# Sheet_brainstorm1.net
KiCad netlist of a schematic drawn in Altium Designer
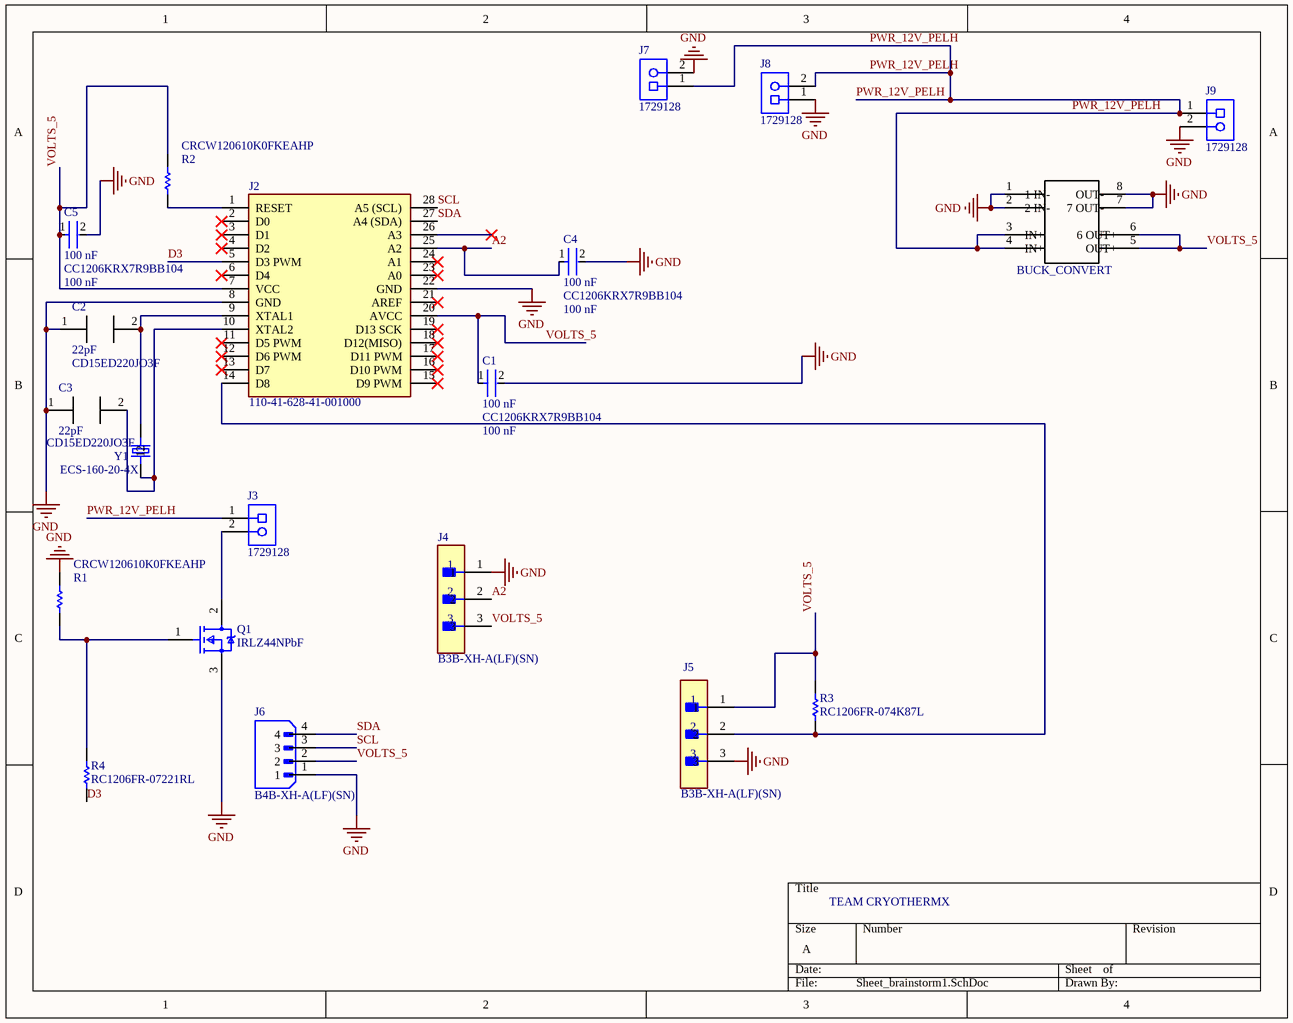
[diagram p0: Sheet_brainstorm1.SchDoc]

(export (version "E")
  (design (tool "Eeschema 10.0.6"))
  (components
    (comp (ref "BUCK_CONVERT")
      (value "buck convertter")
      (footprint "BUCK_CONVERTER")
      (libsource (lib "Integrated_Library_brainstorm1") (part "buck convertter"))
    )
    (comp (ref "C1")
      (value "100 nF")
      (footprint "FP-CC1206-1_25-MFG")
      (description "CAP CER 0.1UF 50V X7R 1206")
      (fields
        (field (name "OCTOPART") "https://octopart.com/cc1206krx7r9bb104-yageo-39467816")
        (field (name "ALTIUM_VALUE") "100 nF")
        (field (name "TOLERANCE") "0.1")
        (field (name "MANUFACTURER PART NUMBER") "CC1206KRX7R9BB104")
      )
      (libsource (lib "Altium Content Vault") (part "11868f565c42a9108669ba33697ecf6"))
    )
    (comp (ref "C2")
      (value "22pF")
      (footprint "PCBComponent_1")
      (description "Mica Capacitor, Mica, 500V, 5% +Tol, 5% -Tol, -20/+100ppm/Cel TC, 0.000022uF, Through Hole Mount")
      (fields
        (field (name "MANUFACTURER") "Cornell Dubilier")
        (field (name "MANUFACTURER PART NUMBER") "CD15ED220JO3F")
      )
      (libsource (lib "Integrated_Library_brainstorm1") (part "CD15ED220JO3F"))
    )
    (comp (ref "C3")
      (value "22pF")
      (footprint "PCBComponent_1")
      (description "Mica Capacitor, Mica, 500V, 5% +Tol, 5% -Tol, -20/+100ppm/Cel TC, 0.000022uF, Through Hole Mount")
      (fields
        (field (name "MANUFACTURER") "Cornell Dubilier")
        (field (name "MANUFACTURER PART NUMBER") "CD15ED220JO3F")
      )
      (libsource (lib "Integrated_Library_brainstorm1") (part "CD15ED220JO3F"))
    )
    (comp (ref "C4")
      (value "100 nF")
      (footprint "FP-CC1206-1_25-MFG")
      (description "CAP CER 0.1UF 50V X7R 1206")
      (fields
        (field (name "OCTOPART") "https://octopart.com/cc1206krx7r9bb104-yageo-39467816")
        (field (name "ALTIUM_VALUE") "100 nF")
        (field (name "TOLERANCE") "0.1")
        (field (name "MANUFACTURER PART NUMBER") "CC1206KRX7R9BB104")
      )
      (libsource (lib "Altium Content Vault") (part "11868f565c42a9108669ba33697ecf6"))
    )
    (comp (ref "C5")
      (value "100 nF")
      (footprint "FP-CC1206-1_25-MFG")
      (description "CAP CER 0.1UF 50V X7R 1206")
      (fields
        (field (name "OCTOPART") "https://octopart.com/cc1206krx7r9bb104-yageo-39467816")
        (field (name "ALTIUM_VALUE") "100 nF")
        (field (name "TOLERANCE") "0.1")
        (field (name "MANUFACTURER PART NUMBER") "CC1206KRX7R9BB104")
      )
      (libsource (lib "Altium Content Vault") (part "11868f565c42a9108669ba33697ecf6"))
    )
    (comp (ref "J2")
      (value "110-41-628-41-001000")
      (footprint "DIPS1524W50P254L3556H419Q28")
      (description "28 (2 x 14) Pos DIP, 0.6 (15.24mm) Row Spacing Socket Gold Through Hole")
      (fields (field (name "MF") "Mill-Max"))
      (libsource (lib "110-41-628-41-001000") (part "110-41-628-41-001000"))
    )
    (comp (ref "J3")
      (value "1729128")
      (footprint "PHOE-1729128-2_V")
      (description "PCB Terminal Block, 13.5 A, 400 V, 2-Pin THD, RoHS, Bulk")
      (fields (field (name "MANUFACTURER") "Phoenix Contact"))
      (libsource (lib "Altium Content Vault") (part "CN-2P-F-R2"))
    )
    (comp (ref "J4")
      (value "B3B-XH-A(LF)(SN)")
      (footprint "FP-B3B-XH-A_LF_SN-MFG")
      (description "CONN HEADER VERT 3POS 2.5MM")
      (libsource (lib "Altium Content Vault") (part "0d3f023dd272f625e17a2be33dea85f"))
    )
    (comp (ref "J5")
      (value "B3B-XH-A(LF)(SN)")
      (footprint "FP-B3B-XH-A_LF_SN-MFG")
      (description "CONN HEADER VERT 3POS 2.5MM")
      (libsource (lib "Altium Content Vault") (part "0d3f023dd272f625e17a2be33dea85f"))
    )
    (comp (ref "J6")
      (value "B4B-XH-A(LF)(SN)")
      (footprint "JST_B4B-XH-A(LF)(SN)")
      (description "Connector Header Through Hole 4 position 0.098 (2.50mm)")
      (fields (field (name "MF") "JST Sales"))
      (libsource (lib "B4B-XH-A_LF__SN_") (part "B4B-XH-A(LF)(SN)"))
    )
    (comp (ref "J7")
      (value "1729128")
      (footprint "PHOE-1729128-2_V")
      (description "PCB Terminal Block, 13.5 A, 400 V, 2-Pin THD, RoHS, Bulk")
      (fields (field (name "MANUFACTURER") "Phoenix Contact"))
      (libsource (lib "") (part "CN-2P-F-R2_1"))
    )
    (comp (ref "J8")
      (value "1729128")
      (footprint "PHOE-1729128-2_V")
      (description "PCB Terminal Block, 13.5 A, 400 V, 2-Pin THD, RoHS, Bulk")
      (fields (field (name "MANUFACTURER") "Phoenix Contact"))
      (libsource (lib "") (part "CN-2P-F-R2_1"))
    )
    (comp (ref "J9")
      (value "1729128")
      (footprint "PHOE-1729128-2_V")
      (description "PCB Terminal Block, 13.5 A, 400 V, 2-Pin THD, RoHS, Bulk")
      (fields (field (name "MANUFACTURER") "Phoenix Contact"))
      (libsource (lib "Altium Content Vault") (part "CN-2P-F-R2"))
    )
    (comp (ref "Q1")
      (value "IRLZ44NPbF")
      (footprint "FP-PG-TO220-3-MFG")
      (description "MOSFET N-CH 55V 47A TO220AB")
      (libsource (lib "Altium Content Vault") (part "b09f7f152735e370c1ea22a33fa83d6"))
    )
    (comp (ref "R1")
      (value "CRCW120610K0FKEAHP")
      (footprint "RESC3116X65X50NL20T20")
      (description "10KOhm R -CRCW120610K0FKEAHP")
      (fields (field (name "MANUFACTURER") "Vishay Dale"))
      (libsource (lib "Altium Content Vault") (part "RES"))
    )
    (comp (ref "R2")
      (value "CRCW120610K0FKEAHP")
      (footprint "RESC3116X65X50NL20T20")
      (description "10KOhm R -CRCW120610K0FKEAHP")
      (fields (field (name "MANUFACTURER") "Vishay Dale"))
      (libsource (lib "Altium Content Vault") (part "RES"))
    )
    (comp (ref "R3")
      (value "RC1206FR-074K87L")
      (footprint "RESC3116X65X40ML10T20")
      (fields (field (name "MANUFACTURER") "Yageo"))
      (libsource (lib "Altium Content Vault") (part "RES"))
    )
    (comp (ref "R4")
      (value "RC1206FR-07221RL")
      (footprint "RESC3116X65X40LL10T20")
      (fields (field (name "MANUFACTURER") "Yageo"))
      (libsource (lib "Altium Content Vault") (part "RES"))
    )
    (comp (ref "Y1")
      (value "ECS-160-20-4X")
      (footprint "XTAL_ECS-160-20-4X")
      (description "16 MHz Â±30ppm Crystal 20pF 40 Ohms HC-49/US")
      (fields (field (name "MF") "ECS Inc."))
      (libsource (lib "ECS-160-20-4X") (part "ECS-160-20-4X"))
    )
  )
  (nets
    (net (code "2") (name "/A2") (class "Default")
      (node (ref "C4") (pin "1") (pinfunction "1_1") (pintype "passive"))
      (node (ref "J2") (pin "25") (pinfunction "A2_25") (pintype "passive"))
      (node (ref "J4") (pin "2") (pinfunction "2_2") (pintype "passive"))
    )
    (net (code "3") (name "/D3") (class "Default")
      (node (ref "J2") (pin "5") (pinfunction "D3_PWM_5") (pintype "passive"))
      (node (ref "R4") (pin "1") (pinfunction "1_1") (pintype "passive"))
    )
    (net (code "4") (name "/PWR_12V_PELH") (class "Default")
      (node (ref "BUCK_CONVERT") (pin "3") (pinfunction "IN+_3") (pintype "passive"))
      (node (ref "BUCK_CONVERT") (pin "4") (pinfunction "IN+_4") (pintype "passive"))
      (node (ref "J3") (pin "1") (pinfunction "1_1") (pintype "passive"))
      (node (ref "J7") (pin "1") (pinfunction "1_1") (pintype "passive"))
      (node (ref "J8") (pin "2") (pinfunction "2_2") (pintype "passive"))
      (node (ref "J9") (pin "1") (pinfunction "1_1") (pintype "passive"))
    )
    (net (code "5") (name "/SCL") (class "Default")
      (node (ref "J2") (pin "28") (pinfunction "A5_(SCL)_28") (pintype "passive"))
      (node (ref "J6") (pin "3") (pinfunction "3_3") (pintype "passive"))
    )
    (net (code "6") (name "/SDA") (class "Default")
      (node (ref "J2") (pin "27") (pinfunction "A4_(SDA)_27") (pintype "passive"))
      (node (ref "J6") (pin "4") (pinfunction "4_4") (pintype "passive"))
    )
    (net (code "7") (name "/VOLTS_5") (class "Default")
      (node (ref "BUCK_CONVERT") (pin "5") (pinfunction "OUT+_5") (pintype "passive"))
      (node (ref "BUCK_CONVERT") (pin "6") (pinfunction "6_OUT+_6") (pintype "passive"))
      (node (ref "C1") (pin "1") (pinfunction "1_1") (pintype "passive"))
      (node (ref "C5") (pin "1") (pinfunction "1_1") (pintype "passive"))
      (node (ref "J2") (pin "20") (pinfunction "AVCC_20") (pintype "passive"))
      (node (ref "J2") (pin "7") (pinfunction "VCC_7") (pintype "passive"))
      (node (ref "J4") (pin "3") (pinfunction "3_3") (pintype "passive"))
      (node (ref "J5") (pin "1") (pinfunction "1_1") (pintype "passive"))
      (node (ref "J6") (pin "2") (pinfunction "2_2") (pintype "passive"))
      (node (ref "R2") (pin "2") (pinfunction "2_2") (pintype "passive"))
      (node (ref "R3") (pin "2") (pinfunction "2_2") (pintype "passive"))
    )
    (net (code "8") (name "GND") (class "Default")
      (node (ref "BUCK_CONVERT") (pin "1") (pinfunction "1_IN-_1") (pintype "passive"))
      (node (ref "BUCK_CONVERT") (pin "2") (pinfunction "2_IN-_2") (pintype "passive"))
      (node (ref "BUCK_CONVERT") (pin "7") (pinfunction "7_OUT-_7") (pintype "passive"))
      (node (ref "BUCK_CONVERT") (pin "8") (pinfunction "OUT-_8") (pintype "passive"))
      (node (ref "C1") (pin "2") (pinfunction "2_2") (pintype "passive"))
      (node (ref "C2") (pin "1") (pinfunction "1_1") (pintype "passive"))
      (node (ref "C3") (pin "1") (pinfunction "1_1") (pintype "passive"))
      (node (ref "C4") (pin "2") (pinfunction "2_2") (pintype "passive"))
      (node (ref "C5") (pin "2") (pinfunction "2_2") (pintype "passive"))
      (node (ref "J2") (pin "22") (pinfunction "GND_22") (pintype "passive"))
      (node (ref "J2") (pin "8") (pinfunction "GND_8") (pintype "passive"))
      (node (ref "J4") (pin "1") (pinfunction "1_1") (pintype "passive"))
      (node (ref "J5") (pin "3") (pinfunction "3_3") (pintype "passive"))
      (node (ref "J6") (pin "1") (pinfunction "1_1") (pintype "passive"))
      (node (ref "J7") (pin "2") (pinfunction "2_2") (pintype "passive"))
      (node (ref "J8") (pin "1") (pinfunction "1_1") (pintype "passive"))
      (node (ref "J9") (pin "2") (pinfunction "2_2") (pintype "passive"))
      (node (ref "Q1") (pin "3") (pinfunction "S_3") (pintype "passive"))
      (node (ref "R1") (pin "2") (pinfunction "2_2") (pintype "passive"))
    )
    (net (code "9") (name "Net-(J2-D8)") (class "Default")
      (node (ref "J2") (pin "14") (pinfunction "D8_14") (pintype "passive"))
      (node (ref "J5") (pin "2") (pinfunction "2_2") (pintype "passive"))
      (node (ref "R3") (pin "1") (pinfunction "1_1") (pintype "passive"))
    )
    (net (code "10") (name "Net-(J2-RESET)") (class "Default")
      (node (ref "J2") (pin "1") (pinfunction "RESET_1") (pintype "passive"))
      (node (ref "R2") (pin "1") (pinfunction "1_1") (pintype "passive"))
    )
    (net (code "11") (name "Net-(J2-XTAL1)") (class "Default")
      (node (ref "C2") (pin "2") (pinfunction "2_2") (pintype "passive"))
      (node (ref "J2") (pin "9") (pinfunction "XTAL1_9") (pintype "passive"))
      (node (ref "Y1") (pin "2") (pinfunction "2_2") (pintype "passive"))
    )
    (net (code "12") (name "Net-(J2-XTAL2)") (class "Default")
      (node (ref "C3") (pin "2") (pinfunction "2_2") (pintype "passive"))
      (node (ref "J2") (pin "10") (pinfunction "XTAL2_10") (pintype "passive"))
      (node (ref "Y1") (pin "1") (pinfunction "1_1") (pintype "passive"))
    )
    (net (code "13") (name "Net-(Q1-D)") (class "Default")
      (node (ref "J3") (pin "2") (pinfunction "2_2") (pintype "passive"))
      (node (ref "Q1") (pin "2") (pinfunction "D_2") (pintype "passive"))
    )
    (net (code "14") (name "Net-(Q1-G)") (class "Default")
      (node (ref "Q1") (pin "1") (pinfunction "G_1") (pintype "passive"))
      (node (ref "R1") (pin "1") (pinfunction "1_1") (pintype "passive"))
      (node (ref "R4") (pin "2") (pinfunction "2_2") (pintype "passive"))
    )
    (net (code "15") (name "unconnected-(J2-A0-Pad23)") (class "Default")
      (node (ref "J2") (pin "23") (pinfunction "A0_23") (pintype "passive+no_connect"))
    )
    (net (code "16") (name "unconnected-(J2-A1-Pad24)") (class "Default")
      (node (ref "J2") (pin "24") (pinfunction "A1_24") (pintype "passive+no_connect"))
    )
    (net (code "17") (name "unconnected-(J2-A3-Pad26)") (class "Default")
      (node (ref "J2") (pin "26") (pinfunction "A3_26") (pintype "passive+no_connect"))
    )
    (net (code "18") (name "unconnected-(J2-AREF-Pad21)") (class "Default")
      (node (ref "J2") (pin "21") (pinfunction "AREF_21") (pintype "passive+no_connect"))
    )
    (net (code "19") (name "unconnected-(J2-D0-Pad2)") (class "Default")
      (node (ref "J2") (pin "2") (pinfunction "D0_2") (pintype "passive+no_connect"))
    )
    (net (code "20") (name "unconnected-(J2-D1-Pad3)") (class "Default")
      (node (ref "J2") (pin "3") (pinfunction "D1_3") (pintype "passive+no_connect"))
    )
    (net (code "21") (name "unconnected-(J2-D2-Pad4)") (class "Default")
      (node (ref "J2") (pin "4") (pinfunction "D2_4") (pintype "passive+no_connect"))
    )
    (net (code "22") (name "unconnected-(J2-D4-Pad6)") (class "Default")
      (node (ref "J2") (pin "6") (pinfunction "D4_6") (pintype "passive+no_connect"))
    )
    (net (code "23") (name "unconnected-(J2-D5_PWM-Pad11)") (class "Default")
      (node (ref "J2") (pin "11") (pinfunction "D5_PWM_11") (pintype "passive+no_connect"))
    )
    (net (code "24") (name "unconnected-(J2-D6_PWM-Pad12)") (class "Default")
      (node (ref "J2") (pin "12") (pinfunction "D6_PWM_12") (pintype "passive+no_connect"))
    )
    (net (code "25") (name "unconnected-(J2-D7-Pad13)") (class "Default")
      (node (ref "J2") (pin "13") (pinfunction "D7_13") (pintype "passive+no_connect"))
    )
    (net (code "26") (name "unconnected-(J2-D9_PWM-Pad15)") (class "Default")
      (node (ref "J2") (pin "15") (pinfunction "D9_PWM_15") (pintype "passive+no_connect"))
    )
    (net (code "27") (name "unconnected-(J2-D10_PWM-Pad16)") (class "Default")
      (node (ref "J2") (pin "16") (pinfunction "D10_PWM_16") (pintype "passive+no_connect"))
    )
    (net (code "28") (name "unconnected-(J2-D11_PWM-Pad17)") (class "Default")
      (node (ref "J2") (pin "17") (pinfunction "D11_PWM_17") (pintype "passive+no_connect"))
    )
    (net (code "29") (name "unconnected-(J2-D12(MISO)-Pad18)") (class "Default")
      (node (ref "J2") (pin "18") (pinfunction "D12(MISO)_18") (pintype "passive+no_connect"))
    )
    (net (code "30") (name "unconnected-(J2-D13_SCK-Pad19)") (class "Default")
      (node (ref "J2") (pin "19") (pinfunction "D13_SCK_19") (pintype "passive+no_connect"))
    )
  )
)
